# power.net
KiCad netlist of a schematic drawn in Altium Designer
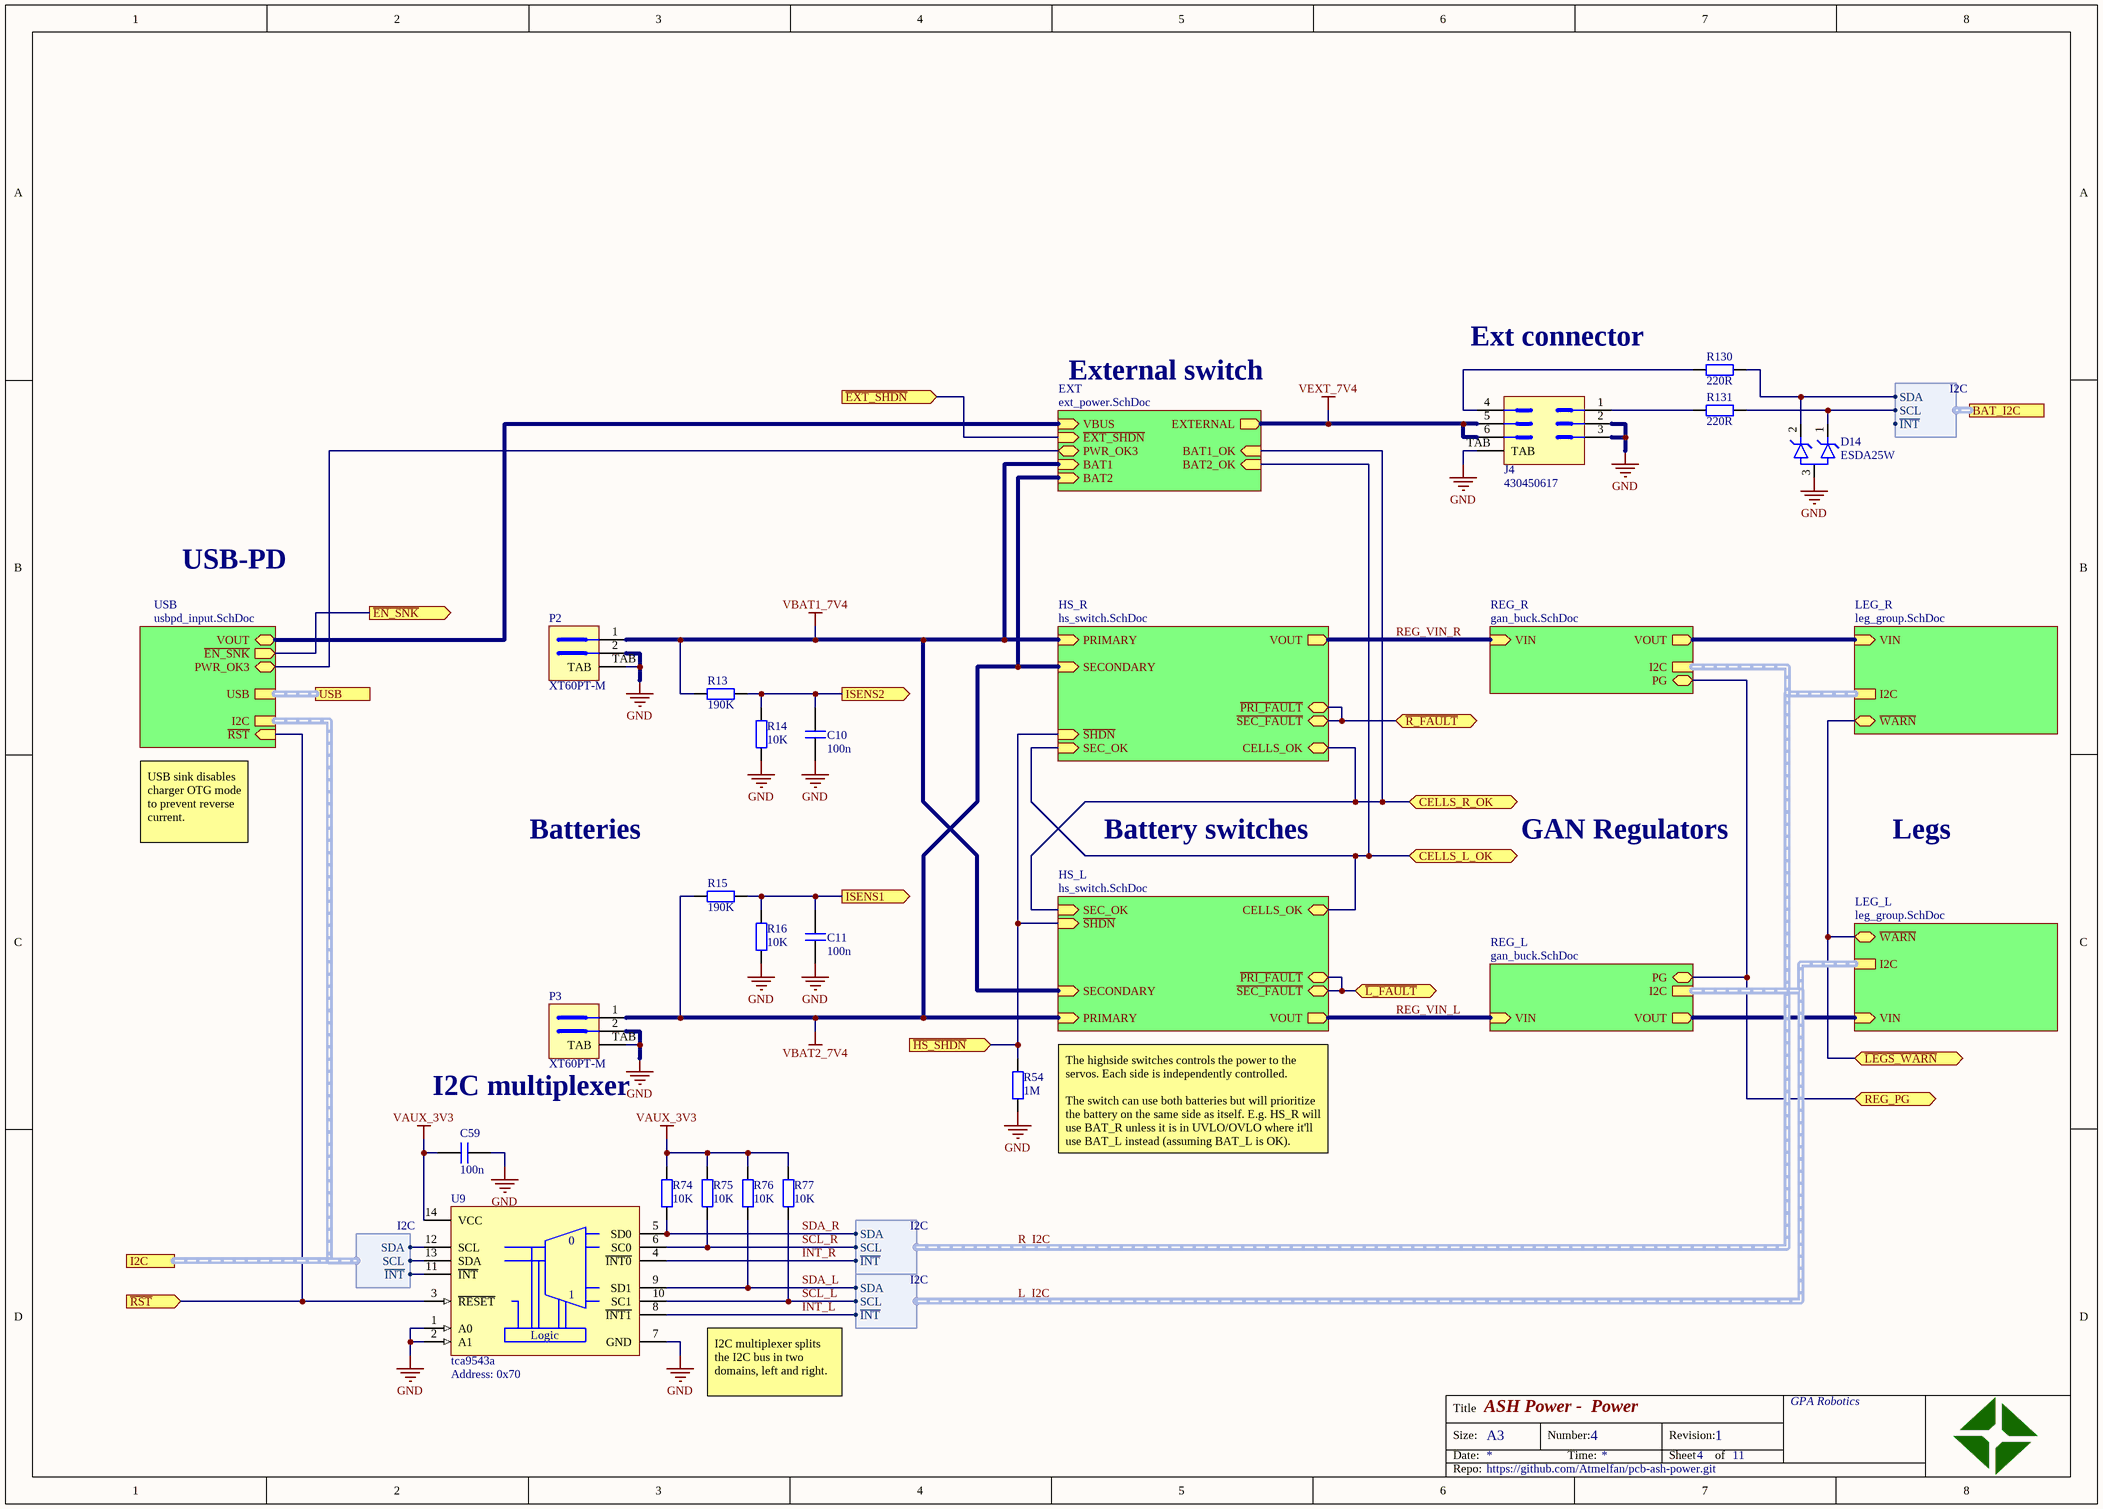
[diagram p0: power.SchDoc]

(export (version "E")
  (design (tool "Eeschema 10.0.6"))
  (components
    (comp (ref "C10")
      (value "100n")
      (footprint "CAPC1005X06N")
      (description "Capacitor")
      (fields (field (name "Comment") "cap"))
      (libsource (lib "lib_passives") (part "cap"))
    )
    (comp (ref "C11")
      (value "100n")
      (footprint "CAPC1005X06N")
      (description "Capacitor")
      (fields (field (name "Comment") "cap"))
      (libsource (lib "lib_passives") (part "cap"))
    )
    (comp (ref "C59")
      (value "100n")
      (footprint "CAPC1005X06N")
      (description "Capacitor")
      (fields (field (name "Comment") "cap"))
      (libsource (lib "lib_passives") (part "cap"))
    )
    (comp (ref "D14")
      (value "ESDA25W")
      (footprint "SOT65P210X110-3N_SOT323-3L")
      (description "TRANSIL array for data protection")
      (libsource (lib "lib_st") (part "esda25w"))
    )
    (comp (ref "J4")
      (value "430450617")
      (footprint "430450617")
      (libsource (lib "lib_molex") (part "430450617"))
    )
    (comp (ref "P2")
      (value "XT60PT-M")
      (footprint "XT60PT-M")
      (libsource (lib "lib_amass") (part "xt60pt-m"))
    )
    (comp (ref "P3")
      (value "XT60PT-M")
      (footprint "XT60PT-M")
      (libsource (lib "lib_amass") (part "xt60pt-m"))
    )
    (comp (ref "R13")
      (value "190K")
      (footprint "RESC1005X04N")
      (description "Resistor")
      (fields (field (name "Comment") "res"))
      (libsource (lib "") (part "res_1"))
    )
    (comp (ref "R14")
      (value "10K")
      (footprint "RESC1005X04N")
      (description "Resistor")
      (fields (field (name "Comment") "res"))
      (libsource (lib "lib_passives") (part "res"))
    )
    (comp (ref "R15")
      (value "190K")
      (footprint "RESC1005X04N")
      (description "Resistor")
      (fields (field (name "Comment") "res"))
      (libsource (lib "") (part "res_1"))
    )
    (comp (ref "R16")
      (value "10K")
      (footprint "RESC1005X04N")
      (description "Resistor")
      (fields (field (name "Comment") "res"))
      (libsource (lib "lib_passives") (part "res"))
    )
    (comp (ref "R54")
      (value "1M")
      (footprint "RESC1005X04N")
      (description "Resistor")
      (fields (field (name "Comment") "res"))
      (libsource (lib "lib_passives") (part "res"))
    )
    (comp (ref "R74")
      (value "10K")
      (footprint "RESC1005X04N")
      (description "Resistor")
      (fields (field (name "Comment") "res"))
      (libsource (lib "lib_passives") (part "res"))
    )
    (comp (ref "R75")
      (value "10K")
      (footprint "RESC1005X04N")
      (description "Resistor")
      (fields (field (name "Comment") "res"))
      (libsource (lib "lib_passives") (part "res"))
    )
    (comp (ref "R76")
      (value "10K")
      (footprint "RESC1005X04N")
      (description "Resistor")
      (fields (field (name "Comment") "res"))
      (libsource (lib "lib_passives") (part "res"))
    )
    (comp (ref "R77")
      (value "10K")
      (footprint "RESC1005X04N")
      (description "Resistor")
      (fields (field (name "Comment") "res"))
      (libsource (lib "lib_passives") (part "res"))
    )
    (comp (ref "R130")
      (value "220R")
      (footprint "RESC1005X04N")
      (description "Resistor")
      (fields (field (name "Comment") "res"))
      (libsource (lib "") (part "res_1"))
    )
    (comp (ref "R131")
      (value "220R")
      (footprint "RESC1005X04N")
      (description "Resistor")
      (fields (field (name "Comment") "res"))
      (libsource (lib "") (part "res_1"))
    )
    (comp (ref "U9")
      (value "tca9543a")
      (footprint "TSOP65P640X120-14N_PCA9543A")
      (description "Low Voltage 2-Channel I2C Bus Switch With Interrupt Logic And Reset")
      (fields (field (name "ADDRESS") "0x70"))
      (libsource (lib "lib_ti") (part "tca9543a"))
    )
  )
  (nets
    (net (code "9") (name "/HS_SHDN") (class "Default")
      (node (ref "R54") (pin "2") (pinfunction "2_2") (pintype "passive"))
    )
    (net (code "10") (name "/INT_L") (class "Default")
      (node (ref "U9") (pin "8") (pinfunction "INT1_8") (pintype "open_collector"))
    )
    (net (code "11") (name "/INT_R") (class "Default")
      (node (ref "U9") (pin "4") (pinfunction "INT0_4") (pintype "open_collector"))
    )
    (net (code "12") (name "/ISENS1") (class "Default")
      (node (ref "C11") (pin "2") (pinfunction "2_2") (pintype "passive"))
      (node (ref "R15") (pin "2") (pinfunction "2_2") (pintype "passive"))
      (node (ref "R16") (pin "2") (pinfunction "2_2") (pintype "passive"))
    )
    (net (code "13") (name "/ISENS2") (class "Default")
      (node (ref "C10") (pin "2") (pinfunction "2_2") (pintype "passive"))
      (node (ref "R13") (pin "2") (pinfunction "2_2") (pintype "passive"))
      (node (ref "R14") (pin "2") (pinfunction "2_2") (pintype "passive"))
    )
    (net (code "21") (name "/RST") (class "Default")
      (node (ref "U9") (pin "3") (pinfunction "RESET_3") (pintype "input"))
    )
    (net (code "24") (name "/SCL_L") (class "Default")
      (node (ref "R77") (pin "1") (pinfunction "1_1") (pintype "passive"))
      (node (ref "U9") (pin "10") (pinfunction "SC1_10") (pintype "open_collector"))
    )
    (net (code "25") (name "/SCL_R") (class "Default")
      (node (ref "R75") (pin "1") (pinfunction "1_1") (pintype "passive"))
      (node (ref "U9") (pin "6") (pinfunction "SC0_6") (pintype "open_collector"))
    )
    (net (code "26") (name "/SDA_L") (class "Default")
      (node (ref "R76") (pin "1") (pinfunction "1_1") (pintype "passive"))
      (node (ref "U9") (pin "9") (pinfunction "SD1_9") (pintype "open_collector"))
    )
    (net (code "27") (name "/SDA_R") (class "Default")
      (node (ref "R74") (pin "1") (pinfunction "1_1") (pintype "passive"))
      (node (ref "U9") (pin "5") (pinfunction "SD0_5") (pintype "open_collector"))
    )
    (net (code "33") (name "GND") (class "Default")
      (node (ref "C10") (pin "1") (pinfunction "1_1") (pintype "passive"))
      (node (ref "C11") (pin "1") (pinfunction "1_1") (pintype "passive"))
      (node (ref "C59") (pin "2") (pinfunction "2_2") (pintype "passive"))
      (node (ref "D14") (pin "3") (pinfunction "3_3") (pintype "passive"))
      (node (ref "J4") (pin "2") (pinfunction "2_2") (pintype "passive"))
      (node (ref "J4") (pin "3") (pinfunction "3_3") (pintype "passive"))
      (node (ref "J4") (pin "TAB") (pinfunction "TAB_TAB") (pintype "passive"))
      (node (ref "P2") (pin "2") (pinfunction "2_2") (pintype "passive"))
      (node (ref "P2") (pin "TAB") (pinfunction "TAB_TAB") (pintype "passive"))
      (node (ref "P3") (pin "2") (pinfunction "2_2") (pintype "passive"))
      (node (ref "P3") (pin "TAB") (pinfunction "TAB_TAB") (pintype "passive"))
      (node (ref "R14") (pin "1") (pinfunction "1_1") (pintype "passive"))
      (node (ref "R16") (pin "1") (pinfunction "1_1") (pintype "passive"))
      (node (ref "R54") (pin "1") (pinfunction "1_1") (pintype "passive"))
      (node (ref "U9") (pin "1") (pinfunction "A0_1") (pintype "input"))
      (node (ref "U9") (pin "2") (pinfunction "A1_2") (pintype "input"))
      (node (ref "U9") (pin "7") (pinfunction "GND_7") (pintype "power_in"))
    )
    (net (code "34") (name "Net-(D14-Pad1)") (class "Default")
      (node (ref "D14") (pin "1") (pinfunction "1_1") (pintype "passive"))
      (node (ref "R131") (pin "2") (pinfunction "2_2") (pintype "passive"))
    )
    (net (code "35") (name "Net-(D14-Pad2)") (class "Default")
      (node (ref "D14") (pin "2") (pinfunction "2_2") (pintype "passive"))
      (node (ref "R130") (pin "2") (pinfunction "2_2") (pintype "passive"))
    )
    (net (code "36") (name "Net-(J4-Pad1)") (class "Default")
      (node (ref "J4") (pin "1") (pinfunction "1_1") (pintype "passive"))
      (node (ref "R131") (pin "1") (pinfunction "1_1") (pintype "passive"))
    )
    (net (code "37") (name "Net-(J4-Pad4)") (class "Default")
      (node (ref "J4") (pin "4") (pinfunction "4_4") (pintype "passive"))
      (node (ref "R130") (pin "1") (pinfunction "1_1") (pintype "passive"))
    )
    (net (code "38") (name "VAUX_3V3") (class "Default")
      (node (ref "C59") (pin "1") (pinfunction "1_1") (pintype "passive"))
      (node (ref "R74") (pin "2") (pinfunction "2_2") (pintype "passive"))
      (node (ref "R75") (pin "2") (pinfunction "2_2") (pintype "passive"))
      (node (ref "R76") (pin "2") (pinfunction "2_2") (pintype "passive"))
      (node (ref "R77") (pin "2") (pinfunction "2_2") (pintype "passive"))
      (node (ref "U9") (pin "14") (pinfunction "VCC_14") (pintype "power_in"))
    )
    (net (code "39") (name "VBAT1_7V4") (class "Default")
      (node (ref "P2") (pin "1") (pinfunction "1_1") (pintype "passive"))
      (node (ref "R13") (pin "1") (pinfunction "1_1") (pintype "passive"))
    )
    (net (code "40") (name "VBAT2_7V4") (class "Default")
      (node (ref "P3") (pin "1") (pinfunction "1_1") (pintype "passive"))
      (node (ref "R15") (pin "1") (pinfunction "1_1") (pintype "passive"))
    )
    (net (code "41") (name "VEXT_7V4") (class "Default")
      (node (ref "J4") (pin "5") (pinfunction "5_5") (pintype "passive"))
      (node (ref "J4") (pin "6") (pinfunction "6_6") (pintype "passive"))
    )
    (net (code "42") (name "unconnected-(U9-INT-Pad11)") (class "Default")
      (node (ref "U9") (pin "11") (pinfunction "INT_11") (pintype "open_collector"))
    )
    (net (code "43") (name "unconnected-(U9-SCL-Pad12)") (class "Default")
      (node (ref "U9") (pin "12") (pinfunction "SCL_12") (pintype "open_collector"))
    )
    (net (code "44") (name "unconnected-(U9-SDA-Pad13)") (class "Default")
      (node (ref "U9") (pin "13") (pinfunction "SDA_13") (pintype "open_collector"))
    )
  )
)
